# STM32.net
KiCad netlist of a schematic drawn in Altium Designer
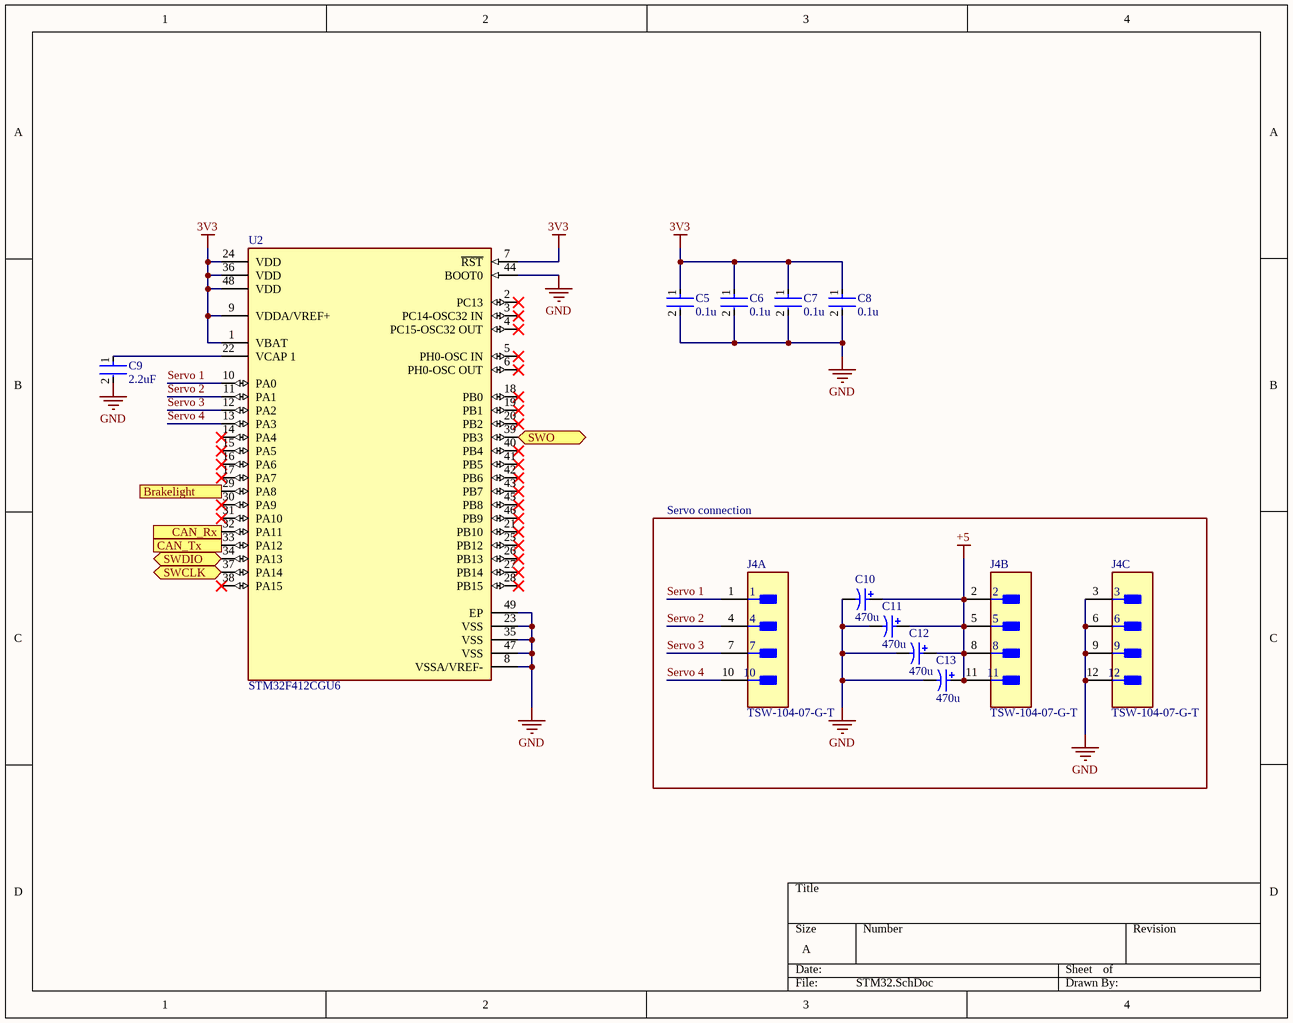
[diagram p0: STM32.SchDoc]

(export (version "E")
  (design (tool "Eeschema 10.0.6"))
  (components
    (comp (ref "C5")
      (value "0.1u")
      (footprint "FP-C0603C-CF-MFG")
      (description "CAP CER 0.1UF 50V X7R 0603")
      (fields (field (name "TOLERANCE") "0.1") (field (name "MANUFACTURER") "KEMET"))
      (libsource (lib "Altium Content Vault") (part "b4654b650e69147ec39a6b967a45e02"))
    )
    (comp (ref "C6")
      (value "0.1u")
      (footprint "FP-C0603C-CF-MFG")
      (description "CAP CER 0.1UF 50V X7R 0603")
      (fields (field (name "TOLERANCE") "0.1") (field (name "MANUFACTURER") "KEMET"))
      (libsource (lib "Altium Content Vault") (part "b4654b650e69147ec39a6b967a45e02"))
    )
    (comp (ref "C7")
      (value "0.1u")
      (footprint "FP-C0603C-CF-MFG")
      (description "CAP CER 0.1UF 50V X7R 0603")
      (fields (field (name "TOLERANCE") "0.1") (field (name "MANUFACTURER") "KEMET"))
      (libsource (lib "Altium Content Vault") (part "b4654b650e69147ec39a6b967a45e02"))
    )
    (comp (ref "C8")
      (value "0.1u")
      (footprint "FP-C0603C-CF-MFG")
      (description "CAP CER 0.1UF 50V X7R 0603")
      (fields (field (name "TOLERANCE") "0.1") (field (name "MANUFACTURER") "KEMET"))
      (libsource (lib "Altium Content Vault") (part "b4654b650e69147ec39a6b967a45e02"))
    )
    (comp (ref "C9")
      (value "2.2uF")
      (footprint "FP-GRM188-0_1-e0_2_0_5-MFG")
      (description "Chip Multilayer Ceramic Capacitors for General Purpose, 0603, 2.2uF, X7R, 15%, 10%, 10V")
      (fields (field (name "VOLTAGE") "10V") (field (name "TOLERANCE") "10%"))
      (libsource (lib "Altium Content Vault") (part "11868f565c42a9108669ba33697ecf6"))
    )
    (comp (ref "C10")
      (value "470u")
      (footprint "PNSC-FP-V-G_V")
      (fields (field (name "MANUFACTURER") "Panasonic"))
      (libsource (lib "Altium Content Vault") (part "CAP-P-2"))
    )
    (comp (ref "C11")
      (value "470u")
      (footprint "PNSC-FP-V-G_V")
      (fields (field (name "MANUFACTURER") "Panasonic"))
      (libsource (lib "Altium Content Vault") (part "CAP-P-2"))
    )
    (comp (ref "C12")
      (value "470u")
      (footprint "PNSC-FP-V-G_V")
      (fields (field (name "MANUFACTURER") "Panasonic"))
      (libsource (lib "Altium Content Vault") (part "CAP-P-2"))
    )
    (comp (ref "C13")
      (value "470u")
      (footprint "PNSC-FP-V-G_V")
      (fields (field (name "MANUFACTURER") "Panasonic"))
      (libsource (lib "Altium Content Vault") (part "CAP-P-2"))
    )
    (comp (ref "J4")
      (value "TSW-104-07-G-T")
      (footprint "FP-TSW-104-07-G-T-MFG")
      (description "CONN HEADER VERT 12POS 2.54MM")
      (fields
        (field (name "MANUFACTURER") "Samtec")
        (field (name "OCTOPART") "https://octopart.com/tsw-104-07-g-t-samtec-8296723")
      )
      (libsource (lib "Altium Content Vault") (part "4835ffea529f644fb4232fae0277480"))
    )
    (comp (ref "U2")
      (value "STM32F412CGU6")
      (footprint "FP-UFQFPN48-A0B9-MFG")
      (description "IC MCU 32BIT 1MB FLASH 48UFQFPN")
      (libsource (lib "Altium Content Vault") (part "7dd92b861eb4b166e7106aa1111722c"))
    )
  )
  (nets
    (net (code "1") (name "+5") (class "Default")
      (node (ref "C10") (pin "1") (pinfunction "1_1") (pintype "passive"))
      (node (ref "C11") (pin "1") (pinfunction "1_1") (pintype "passive"))
      (node (ref "C12") (pin "1") (pinfunction "1_1") (pintype "passive"))
      (node (ref "C13") (pin "1") (pinfunction "1_1") (pintype "passive"))
      (node (ref "J4") (pin "11") (pinfunction "11_11") (pintype "passive"))
      (node (ref "J4") (pin "2") (pinfunction "2_2") (pintype "passive"))
      (node (ref "J4") (pin "5") (pinfunction "5_5") (pintype "passive"))
      (node (ref "J4") (pin "8") (pinfunction "8_8") (pintype "passive"))
    )
    (net (code "2") (name "/Brakelight") (class "Default")
      (node (ref "U2") (pin "29") (pinfunction "PA8_29") (pintype "bidirectional"))
    )
    (net (code "3") (name "/CAN_Rx") (class "Default")
      (node (ref "U2") (pin "32") (pinfunction "PA11_32") (pintype "bidirectional"))
    )
    (net (code "4") (name "/CAN_Tx") (class "Default")
      (node (ref "U2") (pin "33") (pinfunction "PA12_33") (pintype "bidirectional"))
    )
    (net (code "5") (name "/SWCLK") (class "Default")
      (node (ref "U2") (pin "37") (pinfunction "PA14_37") (pintype "bidirectional"))
    )
    (net (code "6") (name "/SWDIO") (class "Default")
      (node (ref "U2") (pin "34") (pinfunction "PA13_34") (pintype "bidirectional"))
    )
    (net (code "7") (name "/SWO") (class "Default")
      (node (ref "U2") (pin "39") (pinfunction "PB3_39") (pintype "bidirectional"))
    )
    (net (code "8") (name "/Servo 1") (class "Default")
      (node (ref "J4") (pin "1") (pinfunction "1_1") (pintype "passive"))
      (node (ref "U2") (pin "10") (pinfunction "PA0_10") (pintype "bidirectional"))
    )
    (net (code "9") (name "/Servo 2") (class "Default")
      (node (ref "J4") (pin "4") (pinfunction "4_4") (pintype "passive"))
      (node (ref "U2") (pin "11") (pinfunction "PA1_11") (pintype "bidirectional"))
    )
    (net (code "10") (name "/Servo 3") (class "Default")
      (node (ref "J4") (pin "7") (pinfunction "7_7") (pintype "passive"))
      (node (ref "U2") (pin "12") (pinfunction "PA2_12") (pintype "bidirectional"))
    )
    (net (code "11") (name "/Servo 4") (class "Default")
      (node (ref "J4") (pin "10") (pinfunction "10_10") (pintype "passive"))
      (node (ref "U2") (pin "13") (pinfunction "PA3_13") (pintype "bidirectional"))
    )
    (net (code "12") (name "3V3") (class "Default")
      (node (ref "C5") (pin "1") (pinfunction "1_1") (pintype "passive"))
      (node (ref "C6") (pin "1") (pinfunction "1_1") (pintype "passive"))
      (node (ref "C7") (pin "1") (pinfunction "1_1") (pintype "passive"))
      (node (ref "C8") (pin "1") (pinfunction "1_1") (pintype "passive"))
      (node (ref "U2") (pin "1") (pinfunction "VBAT_1") (pintype "power_in"))
      (node (ref "U2") (pin "24") (pinfunction "VDD_24") (pintype "power_in"))
      (node (ref "U2") (pin "36") (pinfunction "VDD_36") (pintype "power_in"))
      (node (ref "U2") (pin "48") (pinfunction "VDD_48") (pintype "power_in"))
      (node (ref "U2") (pin "7") (pinfunction "~{RST}_7") (pintype "input"))
      (node (ref "U2") (pin "9") (pinfunction "VDDA/VREF+_9") (pintype "power_in"))
    )
    (net (code "13") (name "GND") (class "Default")
      (node (ref "C10") (pin "2") (pinfunction "2_2") (pintype "passive"))
      (node (ref "C11") (pin "2") (pinfunction "2_2") (pintype "passive"))
      (node (ref "C12") (pin "2") (pinfunction "2_2") (pintype "passive"))
      (node (ref "C13") (pin "2") (pinfunction "2_2") (pintype "passive"))
      (node (ref "C5") (pin "2") (pinfunction "2_2") (pintype "passive"))
      (node (ref "C6") (pin "2") (pinfunction "2_2") (pintype "passive"))
      (node (ref "C7") (pin "2") (pinfunction "2_2") (pintype "passive"))
      (node (ref "C8") (pin "2") (pinfunction "2_2") (pintype "passive"))
      (node (ref "C9") (pin "2") (pinfunction "2_2") (pintype "passive"))
      (node (ref "J4") (pin "12") (pinfunction "12_12") (pintype "passive"))
      (node (ref "J4") (pin "3") (pinfunction "3_3") (pintype "passive"))
      (node (ref "J4") (pin "6") (pinfunction "6_6") (pintype "passive"))
      (node (ref "J4") (pin "9") (pinfunction "9_9") (pintype "passive"))
      (node (ref "U2") (pin "23") (pinfunction "VSS_23") (pintype "power_in"))
      (node (ref "U2") (pin "35") (pinfunction "VSS_35") (pintype "power_in"))
      (node (ref "U2") (pin "44") (pinfunction "BOOT0_44") (pintype "input"))
      (node (ref "U2") (pin "47") (pinfunction "VSS_47") (pintype "power_in"))
      (node (ref "U2") (pin "49") (pinfunction "EP_49") (pintype "passive"))
      (node (ref "U2") (pin "8") (pinfunction "VSSA/VREF-_8") (pintype "power_in"))
    )
    (net (code "14") (name "Net-(U2-VCAP_1)") (class "Default")
      (node (ref "C9") (pin "1") (pinfunction "1_1") (pintype "passive"))
      (node (ref "U2") (pin "22") (pinfunction "VCAP_1_22") (pintype "power_in"))
    )
    (net (code "15") (name "unconnected-(U2-PA4-Pad14)") (class "Default")
      (node (ref "U2") (pin "14") (pinfunction "PA4_14") (pintype "bidirectional+no_connect"))
    )
    (net (code "16") (name "unconnected-(U2-PA5-Pad15)") (class "Default")
      (node (ref "U2") (pin "15") (pinfunction "PA5_15") (pintype "bidirectional+no_connect"))
    )
    (net (code "17") (name "unconnected-(U2-PA6-Pad16)") (class "Default")
      (node (ref "U2") (pin "16") (pinfunction "PA6_16") (pintype "bidirectional+no_connect"))
    )
    (net (code "18") (name "unconnected-(U2-PA7-Pad17)") (class "Default")
      (node (ref "U2") (pin "17") (pinfunction "PA7_17") (pintype "bidirectional+no_connect"))
    )
    (net (code "19") (name "unconnected-(U2-PA9-Pad30)") (class "Default")
      (node (ref "U2") (pin "30") (pinfunction "PA9_30") (pintype "bidirectional+no_connect"))
    )
    (net (code "20") (name "unconnected-(U2-PA10-Pad31)") (class "Default")
      (node (ref "U2") (pin "31") (pinfunction "PA10_31") (pintype "bidirectional+no_connect"))
    )
    (net (code "21") (name "unconnected-(U2-PA15-Pad38)") (class "Default")
      (node (ref "U2") (pin "38") (pinfunction "PA15_38") (pintype "bidirectional+no_connect"))
    )
    (net (code "22") (name "unconnected-(U2-PB0-Pad18)") (class "Default")
      (node (ref "U2") (pin "18") (pinfunction "PB0_18") (pintype "bidirectional+no_connect"))
    )
    (net (code "23") (name "unconnected-(U2-PB1-Pad19)") (class "Default")
      (node (ref "U2") (pin "19") (pinfunction "PB1_19") (pintype "bidirectional+no_connect"))
    )
    (net (code "24") (name "unconnected-(U2-PB2-Pad20)") (class "Default")
      (node (ref "U2") (pin "20") (pinfunction "PB2_20") (pintype "bidirectional+no_connect"))
    )
    (net (code "25") (name "unconnected-(U2-PB4-Pad40)") (class "Default")
      (node (ref "U2") (pin "40") (pinfunction "PB4_40") (pintype "bidirectional+no_connect"))
    )
    (net (code "26") (name "unconnected-(U2-PB5-Pad41)") (class "Default")
      (node (ref "U2") (pin "41") (pinfunction "PB5_41") (pintype "bidirectional+no_connect"))
    )
    (net (code "27") (name "unconnected-(U2-PB6-Pad42)") (class "Default")
      (node (ref "U2") (pin "42") (pinfunction "PB6_42") (pintype "bidirectional+no_connect"))
    )
    (net (code "28") (name "unconnected-(U2-PB7-Pad43)") (class "Default")
      (node (ref "U2") (pin "43") (pinfunction "PB7_43") (pintype "bidirectional+no_connect"))
    )
    (net (code "29") (name "unconnected-(U2-PB8-Pad45)") (class "Default")
      (node (ref "U2") (pin "45") (pinfunction "PB8_45") (pintype "bidirectional+no_connect"))
    )
    (net (code "30") (name "unconnected-(U2-PB9-Pad46)") (class "Default")
      (node (ref "U2") (pin "46") (pinfunction "PB9_46") (pintype "bidirectional+no_connect"))
    )
    (net (code "31") (name "unconnected-(U2-PB10-Pad21)") (class "Default")
      (node (ref "U2") (pin "21") (pinfunction "PB10_21") (pintype "bidirectional+no_connect"))
    )
    (net (code "32") (name "unconnected-(U2-PB12-Pad25)") (class "Default")
      (node (ref "U2") (pin "25") (pinfunction "PB12_25") (pintype "bidirectional+no_connect"))
    )
    (net (code "33") (name "unconnected-(U2-PB13-Pad26)") (class "Default")
      (node (ref "U2") (pin "26") (pinfunction "PB13_26") (pintype "bidirectional+no_connect"))
    )
    (net (code "34") (name "unconnected-(U2-PB14-Pad27)") (class "Default")
      (node (ref "U2") (pin "27") (pinfunction "PB14_27") (pintype "bidirectional+no_connect"))
    )
    (net (code "35") (name "unconnected-(U2-PB15-Pad28)") (class "Default")
      (node (ref "U2") (pin "28") (pinfunction "PB15_28") (pintype "bidirectional+no_connect"))
    )
    (net (code "36") (name "unconnected-(U2-PC13-Pad2)") (class "Default")
      (node (ref "U2") (pin "2") (pinfunction "PC13_2") (pintype "bidirectional+no_connect"))
    )
    (net (code "37") (name "unconnected-(U2-PC14-OSC32_IN-Pad3)") (class "Default")
      (node (ref "U2") (pin "3") (pinfunction "PC14-OSC32_IN_3") (pintype "bidirectional+no_connect"))
    )
    (net (code "38") (name "unconnected-(U2-PC15-OSC32_OUT-Pad4)") (class "Default")
      (node (ref "U2") (pin "4") (pinfunction "PC15-OSC32_OUT_4") (pintype "bidirectional+no_connect"))
    )
    (net (code "39") (name "unconnected-(U2-PH0-OSC_IN-Pad5)") (class "Default")
      (node (ref "U2") (pin "5") (pinfunction "PH0-OSC_IN_5") (pintype "bidirectional+no_connect"))
    )
    (net (code "40") (name "unconnected-(U2-PH0-OSC_OUT-Pad6)") (class "Default")
      (node (ref "U2") (pin "6") (pinfunction "PH0-OSC_OUT_6") (pintype "bidirectional+no_connect"))
    )
  )
)
